# McuPro.net
KiCad netlist of a schematic drawn in Altium Designer
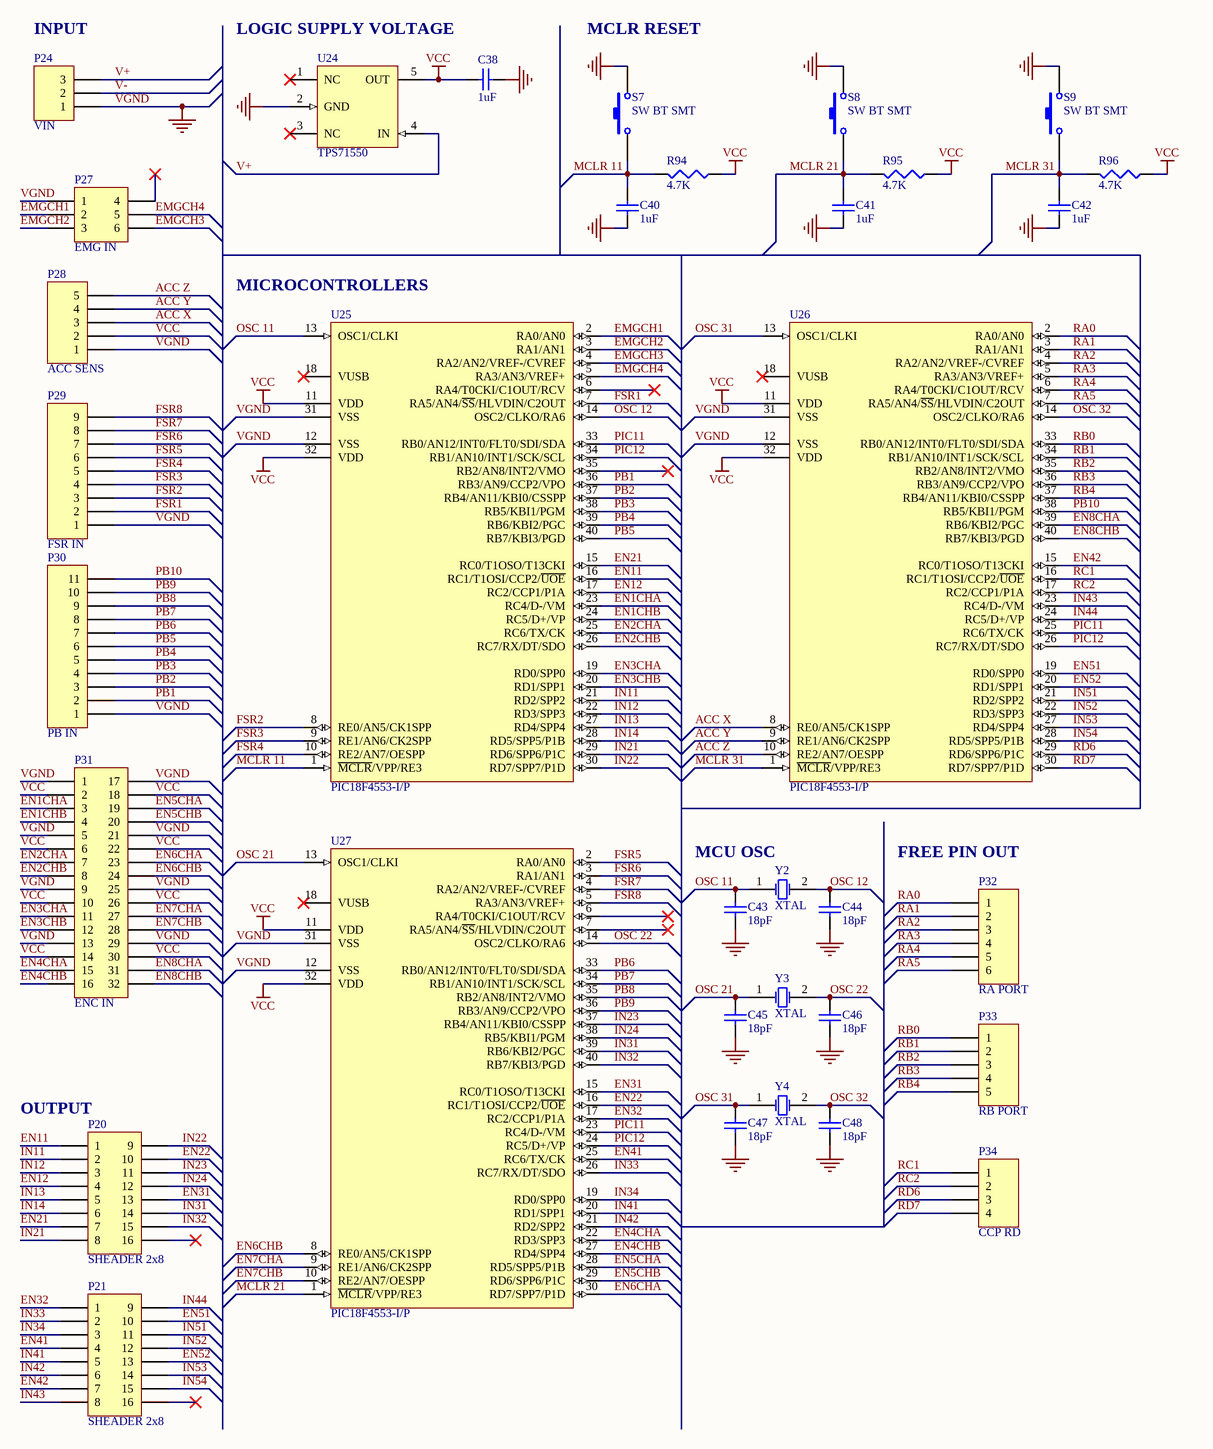
[diagram p0: McuPro.SchDoc]

(export (version "E")
  (design (tool "Eeschema 10.0.6"))
  (components
    (comp (ref "C38")
      (value "1uF")
      (footprint "CAPC2012M")
      (description "Capacitor (Semiconductor SIM Model)")
      (fields (field (name "Comment") "Cap Semi") (field (name "PUBLISHER") "Altium Limited"))
      (libsource (lib "Miscellaneous Devices") (part "Cap Semi"))
    )
    (comp (ref "C40")
      (value "1uF")
      (footprint "CAPC2012M")
      (description "Capacitor (Semiconductor SIM Model)")
      (fields (field (name "Comment") "Cap Semi") (field (name "PUBLISHER") "Altium Limited"))
      (libsource (lib "Miscellaneous Devices") (part "Cap Semi"))
    )
    (comp (ref "C41")
      (value "1uF")
      (footprint "CAPC2012M")
      (description "Capacitor (Semiconductor SIM Model)")
      (fields (field (name "Comment") "Cap Semi") (field (name "PUBLISHER") "Altium Limited"))
      (libsource (lib "Miscellaneous Devices") (part "Cap Semi"))
    )
    (comp (ref "C42")
      (value "1uF")
      (footprint "CAPC2012M")
      (description "Capacitor (Semiconductor SIM Model)")
      (fields (field (name "Comment") "Cap Semi") (field (name "PUBLISHER") "Altium Limited"))
      (libsource (lib "Miscellaneous Devices") (part "Cap Semi"))
    )
    (comp (ref "C43")
      (value "18pF")
      (footprint "C1206")
      (description "Capacitor (Semiconductor SIM Model)")
      (fields (field (name "Comment") "Cap Semi") (field (name "PUBLISHER") "Altium Limited"))
      (libsource (lib "Miscellaneous Devices") (part "Cap Semi"))
    )
    (comp (ref "C44")
      (value "18pF")
      (footprint "C1206")
      (description "Capacitor (Semiconductor SIM Model)")
      (fields (field (name "Comment") "Cap Semi") (field (name "PUBLISHER") "Altium Limited"))
      (libsource (lib "Miscellaneous Devices") (part "Cap Semi"))
    )
    (comp (ref "C45")
      (value "18pF")
      (footprint "C1206")
      (description "Capacitor (Semiconductor SIM Model)")
      (fields (field (name "Comment") "Cap Semi") (field (name "PUBLISHER") "Altium Limited"))
      (libsource (lib "Miscellaneous Devices") (part "Cap Semi"))
    )
    (comp (ref "C46")
      (value "18pF")
      (footprint "C1206")
      (description "Capacitor (Semiconductor SIM Model)")
      (fields (field (name "Comment") "Cap Semi") (field (name "PUBLISHER") "Altium Limited"))
      (libsource (lib "Miscellaneous Devices") (part "Cap Semi"))
    )
    (comp (ref "C47")
      (value "18pF")
      (footprint "C1206")
      (description "Capacitor (Semiconductor SIM Model)")
      (fields (field (name "Comment") "Cap Semi") (field (name "PUBLISHER") "Altium Limited"))
      (libsource (lib "Miscellaneous Devices") (part "Cap Semi"))
    )
    (comp (ref "C48")
      (value "18pF")
      (footprint "C1206")
      (description "Capacitor (Semiconductor SIM Model)")
      (fields (field (name "Comment") "Cap Semi") (field (name "PUBLISHER") "Altium Limited"))
      (libsource (lib "Miscellaneous Devices") (part "Cap Semi"))
    )
    (comp (ref "P20")
      (value "SHEADER 2x8")
      (footprint "SHBH 2X8")
      (description "Shrouded Box Header: 2x8-Pin, 0.100\" (2.54 mm) Male")
      (libsource (lib "LitoLibrary") (part "SB Header 2x8"))
    )
    (comp (ref "P21")
      (value "SHEADER 2x8")
      (footprint "SHBH 2X8")
      (description "Shrouded Box Header: 2x8-Pin, 0.100\" (2.54 mm) Male")
      (libsource (lib "LitoLibrary") (part "SB Header 2x8"))
    )
    (comp (ref "P24")
      (value "VIN")
      (footprint "AZUL5-3")
      (description "Header, 3-Pin")
      (fields (field (name "PUBLISHER") "Altium Limited"))
      (libsource (lib "Miscellaneous Connectors") (part "Header 3"))
    )
    (comp (ref "P27")
      (value "EMG IN")
      (footprint "SHBH 2x3")
      (description "Shrouded Box Header: 2x8-Pin, 0.100\" (2.54 mm) Male")
      (libsource (lib "LitoLibrary") (part "SB Header 2x3"))
    )
    (comp (ref "P28")
      (value "ACC SENS")
      (footprint "HDR1X5H")
      (description "Header, 5-Pin, Right Angle")
      (fields (field (name "PUBLISHER") "Altium Limited"))
      (libsource (lib "Miscellaneous Connectors") (part "Header 5H"))
    )
    (comp (ref "P29")
      (value "FSR IN")
      (footprint "HDR1X9H")
      (description "Header, 9-Pin, Right Angle")
      (fields (field (name "PUBLISHER") "Altium Limited"))
      (libsource (lib "Miscellaneous Connectors") (part "Header 9H"))
    )
    (comp (ref "P30")
      (value "PB IN")
      (footprint "HDR1X11H")
      (description "Header, 11-Pin, Right Angle")
      (fields (field (name "PUBLISHER") "Altium Limited"))
      (libsource (lib "Miscellaneous Connectors") (part "Header 11H"))
    )
    (comp (ref "P31")
      (value "ENC IN")
      (footprint "HDR2X16_CEN")
      (description "Header, 16-Pin, Dual row")
      (fields (field (name "PUBLISHER") "Altium Limited"))
      (libsource (lib "Miscellaneous Connectors") (part "Header 16X2A"))
    )
    (comp (ref "P32")
      (value "RA PORT")
      (footprint "HDR1X6")
      (description "Header, 6-Pin")
      (fields (field (name "PUBLISHER") "Altium Limited"))
      (libsource (lib "Miscellaneous Connectors") (part "Header 6"))
    )
    (comp (ref "P33")
      (value "RB PORT")
      (footprint "HDR1X5")
      (description "Header, 5-Pin")
      (fields (field (name "PUBLISHER") "Altium Limited"))
      (libsource (lib "Miscellaneous Connectors") (part "Header 5"))
    )
    (comp (ref "P34")
      (value "CCP RD")
      (footprint "HDR1X4")
      (description "Header, 4-Pin")
      (fields (field (name "PUBLISHER") "Altium Limited"))
      (libsource (lib "Miscellaneous Connectors") (part "Header 4"))
    )
    (comp (ref "R94")
      (value "4.7K")
      (footprint "RESC3225M")
      (description "Resistor")
      (fields (field (name "Comment") "Res3") (field (name "PUBLISHER") "Altium Limited"))
      (libsource (lib "Miscellaneous Devices") (part "Res3"))
    )
    (comp (ref "R95")
      (value "4.7K")
      (footprint "RESC3225M")
      (description "Resistor")
      (fields (field (name "Comment") "Res3") (field (name "PUBLISHER") "Altium Limited"))
      (libsource (lib "Miscellaneous Devices") (part "Res3"))
    )
    (comp (ref "R96")
      (value "4.7K")
      (footprint "RESC3225M")
      (description "Resistor")
      (fields (field (name "Comment") "Res3") (field (name "PUBLISHER") "Altium Limited"))
      (libsource (lib "Miscellaneous Devices") (part "Res3"))
    )
    (comp (ref "S7")
      (value "SW BT SMT")
      (footprint "PBOTTON SMT4")
      (description "Pushbutton Switches FSM2JSMAASTR=6MM TACT SWITCH,")
      (libsource (lib "LitoLibrary") (part "SW PB 6mm"))
    )
    (comp (ref "S8")
      (value "SW BT SMT")
      (footprint "PBOTTON SMT4")
      (description "Pushbutton Switches FSM2JSMAASTR=6MM TACT SWITCH,")
      (libsource (lib "LitoLibrary") (part "SW PB 6mm"))
    )
    (comp (ref "S9")
      (value "SW BT SMT")
      (footprint "PBOTTON SMT4")
      (description "Pushbutton Switches FSM2JSMAASTR=6MM TACT SWITCH,")
      (libsource (lib "LitoLibrary") (part "SW PB 6mm"))
    )
    (comp (ref "U24")
      (value "TPS71550")
      (footprint "SOT353-5L")
      (libsource (lib "LitoLibrary") (part "TPS71550"))
    )
    (comp (ref "U25")
      (value "PIC18F4553-I/P")
      (footprint "PDIP600-P40")
      (fields (field (name "PUBLISHER") "Altium Limited"))
      (libsource (lib "Microchip Microcontroller 8-Bit PIC18") (part "PIC18F4553-I/P"))
    )
    (comp (ref "U26")
      (value "PIC18F4553-I/P")
      (footprint "PDIP600-P40")
      (fields (field (name "PUBLISHER") "Altium Limited"))
      (libsource (lib "Microchip Microcontroller 8-Bit PIC18") (part "PIC18F4553-I/P"))
    )
    (comp (ref "U27")
      (value "PIC18F4553-I/P")
      (footprint "PDIP600-P40")
      (fields (field (name "PUBLISHER") "Altium Limited"))
      (libsource (lib "Microchip Microcontroller 8-Bit PIC18") (part "PIC18F4553-I/P"))
    )
    (comp (ref "Y2")
      (value "XTAL")
      (footprint "XTAL-1")
      (description "Crystal Oscillator")
      (fields (field (name "PUBLISHER") "Altium Limited"))
      (libsource (lib "Miscellaneous Devices") (part "XTAL"))
    )
    (comp (ref "Y3")
      (value "XTAL")
      (footprint "XTAL-1")
      (description "Crystal Oscillator")
      (fields (field (name "PUBLISHER") "Altium Limited"))
      (libsource (lib "Miscellaneous Devices") (part "XTAL"))
    )
    (comp (ref "Y4")
      (value "XTAL")
      (footprint "XTAL-1")
      (description "Crystal Oscillator")
      (fields (field (name "PUBLISHER") "Altium Limited"))
      (libsource (lib "Miscellaneous Devices") (part "XTAL"))
    )
  )
  (nets
    (net (code "1") (name "/ACC X") (class "Default")
      (node (ref "P28") (pin "3") (pinfunction "3_3") (pintype "passive"))
      (node (ref "U26") (pin "8") (pinfunction "RE0/AN5/CK1SPP_8") (pintype "bidirectional"))
    )
    (net (code "2") (name "/ACC Y") (class "Default")
      (node (ref "P28") (pin "4") (pinfunction "4_4") (pintype "passive"))
      (node (ref "U26") (pin "9") (pinfunction "RE1/AN6/CK2SPP_9") (pintype "bidirectional"))
    )
    (net (code "3") (name "/ACC Z") (class "Default")
      (node (ref "P28") (pin "5") (pinfunction "5_5") (pintype "passive"))
      (node (ref "U26") (pin "10") (pinfunction "RE2/AN7/OESPP_10") (pintype "bidirectional"))
    )
    (net (code "4") (name "/EMGCH1") (class "Default")
      (node (ref "P27") (pin "2") (pinfunction "2_2") (pintype "passive"))
      (node (ref "U25") (pin "2") (pinfunction "RA0/AN0_2") (pintype "bidirectional"))
    )
    (net (code "5") (name "/EMGCH2") (class "Default")
      (node (ref "P27") (pin "3") (pinfunction "3_3") (pintype "passive"))
      (node (ref "U25") (pin "3") (pinfunction "RA1/AN1_3") (pintype "bidirectional"))
    )
    (net (code "6") (name "/EMGCH3") (class "Default")
      (node (ref "P27") (pin "6") (pinfunction "6_6") (pintype "passive"))
      (node (ref "U25") (pin "4") (pinfunction "RA2/AN2/VREF-/CVREF_4") (pintype "bidirectional"))
    )
    (net (code "7") (name "/EMGCH4") (class "Default")
      (node (ref "P27") (pin "5") (pinfunction "5_5") (pintype "passive"))
      (node (ref "U25") (pin "5") (pinfunction "RA3/AN3/VREF+_5") (pintype "bidirectional"))
    )
    (net (code "8") (name "/EN1CHA") (class "Default")
      (node (ref "P31") (pin "3") (pinfunction "3_3") (pintype "passive"))
      (node (ref "U25") (pin "23") (pinfunction "RC4/D-/VM_23") (pintype "bidirectional"))
    )
    (net (code "9") (name "/EN1CHB") (class "Default")
      (node (ref "P31") (pin "4") (pinfunction "4_4") (pintype "passive"))
      (node (ref "U25") (pin "24") (pinfunction "RC5/D+/VP_24") (pintype "bidirectional"))
    )
    (net (code "10") (name "/EN2CHA") (class "Default")
      (node (ref "P31") (pin "7") (pinfunction "7_7") (pintype "passive"))
      (node (ref "U25") (pin "25") (pinfunction "RC6/TX/CK_25") (pintype "bidirectional"))
    )
    (net (code "11") (name "/EN2CHB") (class "Default")
      (node (ref "P31") (pin "8") (pinfunction "8_8") (pintype "passive"))
      (node (ref "U25") (pin "26") (pinfunction "RC7/RX/DT/SDO_26") (pintype "bidirectional"))
    )
    (net (code "12") (name "/EN3CHA") (class "Default")
      (node (ref "P31") (pin "11") (pinfunction "11_11") (pintype "passive"))
      (node (ref "U25") (pin "19") (pinfunction "RD0/SPP0_19") (pintype "bidirectional"))
    )
    (net (code "13") (name "/EN3CHB") (class "Default")
      (node (ref "P31") (pin "12") (pinfunction "12_12") (pintype "passive"))
      (node (ref "U25") (pin "20") (pinfunction "RD1/SPP1_20") (pintype "bidirectional"))
    )
    (net (code "14") (name "/EN4CHA") (class "Default")
      (node (ref "P31") (pin "15") (pinfunction "15_15") (pintype "passive"))
      (node (ref "U27") (pin "22") (pinfunction "RD3/SPP3_22") (pintype "bidirectional"))
    )
    (net (code "15") (name "/EN4CHB") (class "Default")
      (node (ref "P31") (pin "16") (pinfunction "16_16") (pintype "passive"))
      (node (ref "U27") (pin "27") (pinfunction "RD4/SPP4_27") (pintype "bidirectional"))
    )
    (net (code "16") (name "/EN5CHA") (class "Default")
      (node (ref "P31") (pin "19") (pinfunction "19_19") (pintype "passive"))
      (node (ref "U27") (pin "28") (pinfunction "RD5/SPP5/P1B_28") (pintype "bidirectional"))
    )
    (net (code "17") (name "/EN5CHB") (class "Default")
      (node (ref "P31") (pin "20") (pinfunction "20_20") (pintype "passive"))
      (node (ref "U27") (pin "29") (pinfunction "RD6/SPP6/P1C_29") (pintype "bidirectional"))
    )
    (net (code "18") (name "/EN6CHA") (class "Default")
      (node (ref "P31") (pin "23") (pinfunction "23_23") (pintype "passive"))
      (node (ref "U27") (pin "30") (pinfunction "RD7/SPP7/P1D_30") (pintype "bidirectional"))
    )
    (net (code "19") (name "/EN6CHB") (class "Default")
      (node (ref "P31") (pin "24") (pinfunction "24_24") (pintype "passive"))
      (node (ref "U27") (pin "8") (pinfunction "RE0/AN5/CK1SPP_8") (pintype "bidirectional"))
    )
    (net (code "20") (name "/EN7CHA") (class "Default")
      (node (ref "P31") (pin "27") (pinfunction "27_27") (pintype "passive"))
      (node (ref "U27") (pin "9") (pinfunction "RE1/AN6/CK2SPP_9") (pintype "bidirectional"))
    )
    (net (code "21") (name "/EN7CHB") (class "Default")
      (node (ref "P31") (pin "28") (pinfunction "28_28") (pintype "passive"))
      (node (ref "U27") (pin "10") (pinfunction "RE2/AN7/OESPP_10") (pintype "bidirectional"))
    )
    (net (code "22") (name "/EN8CHA") (class "Default")
      (node (ref "P31") (pin "31") (pinfunction "31_31") (pintype "passive"))
      (node (ref "U26") (pin "39") (pinfunction "RB6/KBI2/PGC_39") (pintype "bidirectional"))
    )
    (net (code "23") (name "/EN8CHB") (class "Default")
      (node (ref "P31") (pin "32") (pinfunction "32_32") (pintype "passive"))
      (node (ref "U26") (pin "40") (pinfunction "RB7/KBI3/PGD_40") (pintype "bidirectional"))
    )
    (net (code "24") (name "/EN11") (class "Default")
      (node (ref "P20") (pin "1") (pinfunction "1_1") (pintype "passive"))
      (node (ref "U25") (pin "16") (pinfunction "RC1/T1OSI/CCP2/~{UOE}_16") (pintype "bidirectional"))
    )
    (net (code "25") (name "/EN12") (class "Default")
      (node (ref "P20") (pin "4") (pinfunction "4_4") (pintype "passive"))
      (node (ref "U25") (pin "17") (pinfunction "RC2/CCP1/P1A_17") (pintype "bidirectional"))
    )
    (net (code "26") (name "/EN21") (class "Default")
      (node (ref "P20") (pin "7") (pinfunction "7_7") (pintype "passive"))
      (node (ref "U25") (pin "15") (pinfunction "RC0/T1OSO/T13CKI_15") (pintype "bidirectional"))
    )
    (net (code "27") (name "/EN22") (class "Default")
      (node (ref "P20") (pin "10") (pinfunction "10_10") (pintype "passive"))
      (node (ref "U27") (pin "16") (pinfunction "RC1/T1OSI/CCP2/~{UOE}_16") (pintype "bidirectional"))
    )
    (net (code "28") (name "/EN31") (class "Default")
      (node (ref "P20") (pin "13") (pinfunction "13_13") (pintype "passive"))
      (node (ref "U27") (pin "15") (pinfunction "RC0/T1OSO/T13CKI_15") (pintype "bidirectional"))
    )
    (net (code "29") (name "/EN32") (class "Default")
      (node (ref "P21") (pin "1") (pinfunction "1_1") (pintype "passive"))
      (node (ref "U27") (pin "17") (pinfunction "RC2/CCP1/P1A_17") (pintype "bidirectional"))
    )
    (net (code "30") (name "/EN41") (class "Default")
      (node (ref "P21") (pin "4") (pinfunction "4_4") (pintype "passive"))
      (node (ref "U27") (pin "25") (pinfunction "RC6/TX/CK_25") (pintype "bidirectional"))
    )
    (net (code "31") (name "/EN42") (class "Default")
      (node (ref "P21") (pin "7") (pinfunction "7_7") (pintype "passive"))
      (node (ref "U26") (pin "15") (pinfunction "RC0/T1OSO/T13CKI_15") (pintype "bidirectional"))
    )
    (net (code "32") (name "/EN51") (class "Default")
      (node (ref "P21") (pin "10") (pinfunction "10_10") (pintype "passive"))
      (node (ref "U26") (pin "19") (pinfunction "RD0/SPP0_19") (pintype "bidirectional"))
    )
    (net (code "33") (name "/EN52") (class "Default")
      (node (ref "P21") (pin "13") (pinfunction "13_13") (pintype "passive"))
      (node (ref "U26") (pin "20") (pinfunction "RD1/SPP1_20") (pintype "bidirectional"))
    )
    (net (code "34") (name "/FSR1") (class "Default")
      (node (ref "P29") (pin "2") (pinfunction "2_2") (pintype "passive"))
      (node (ref "U25") (pin "7") (pinfunction "RA5/AN4/~{SS}/HLVDIN/C2OUT_7") (pintype "bidirectional"))
    )
    (net (code "35") (name "/FSR2") (class "Default")
      (node (ref "P29") (pin "3") (pinfunction "3_3") (pintype "passive"))
      (node (ref "U25") (pin "8") (pinfunction "RE0/AN5/CK1SPP_8") (pintype "bidirectional"))
    )
    (net (code "36") (name "/FSR3") (class "Default")
      (node (ref "P29") (pin "4") (pinfunction "4_4") (pintype "passive"))
      (node (ref "U25") (pin "9") (pinfunction "RE1/AN6/CK2SPP_9") (pintype "bidirectional"))
    )
    (net (code "37") (name "/FSR4") (class "Default")
      (node (ref "P29") (pin "5") (pinfunction "5_5") (pintype "passive"))
      (node (ref "U25") (pin "10") (pinfunction "RE2/AN7/OESPP_10") (pintype "bidirectional"))
    )
    (net (code "38") (name "/FSR5") (class "Default")
      (node (ref "P29") (pin "6") (pinfunction "6_6") (pintype "passive"))
      (node (ref "U27") (pin "2") (pinfunction "RA0/AN0_2") (pintype "bidirectional"))
    )
    (net (code "39") (name "/FSR6") (class "Default")
      (node (ref "P29") (pin "7") (pinfunction "7_7") (pintype "passive"))
      (node (ref "U27") (pin "3") (pinfunction "RA1/AN1_3") (pintype "bidirectional"))
    )
    (net (code "40") (name "/FSR7") (class "Default")
      (node (ref "P29") (pin "8") (pinfunction "8_8") (pintype "passive"))
      (node (ref "U27") (pin "4") (pinfunction "RA2/AN2/VREF-/CVREF_4") (pintype "bidirectional"))
    )
    (net (code "41") (name "/FSR8") (class "Default")
      (node (ref "P29") (pin "9") (pinfunction "9_9") (pintype "passive"))
      (node (ref "U27") (pin "5") (pinfunction "RA3/AN3/VREF+_5") (pintype "bidirectional"))
    )
    (net (code "42") (name "/IN11") (class "Default")
      (node (ref "P20") (pin "2") (pinfunction "2_2") (pintype "passive"))
      (node (ref "U25") (pin "21") (pinfunction "RD2/SPP2_21") (pintype "bidirectional"))
    )
    (net (code "43") (name "/IN12") (class "Default")
      (node (ref "P20") (pin "3") (pinfunction "3_3") (pintype "passive"))
      (node (ref "U25") (pin "22") (pinfunction "RD3/SPP3_22") (pintype "bidirectional"))
    )
    (net (code "44") (name "/IN13") (class "Default")
      (node (ref "P20") (pin "5") (pinfunction "5_5") (pintype "passive"))
      (node (ref "U25") (pin "27") (pinfunction "RD4/SPP4_27") (pintype "bidirectional"))
    )
    (net (code "45") (name "/IN14") (class "Default")
      (node (ref "P20") (pin "6") (pinfunction "6_6") (pintype "passive"))
      (node (ref "U25") (pin "28") (pinfunction "RD5/SPP5/P1B_28") (pintype "bidirectional"))
    )
    (net (code "46") (name "/IN21") (class "Default")
      (node (ref "P20") (pin "8") (pinfunction "8_8") (pintype "passive"))
      (node (ref "U25") (pin "29") (pinfunction "RD6/SPP6/P1C_29") (pintype "bidirectional"))
    )
    (net (code "47") (name "/IN22") (class "Default")
      (node (ref "P20") (pin "9") (pinfunction "9_9") (pintype "passive"))
      (node (ref "U25") (pin "30") (pinfunction "RD7/SPP7/P1D_30") (pintype "bidirectional"))
    )
    (net (code "48") (name "/IN23") (class "Default")
      (node (ref "P20") (pin "11") (pinfunction "11_11") (pintype "passive"))
      (node (ref "U27") (pin "37") (pinfunction "RB4/AN11/KBI0/CSSPP_37") (pintype "bidirectional"))
    )
    (net (code "49") (name "/IN24") (class "Default")
      (node (ref "P20") (pin "12") (pinfunction "12_12") (pintype "passive"))
      (node (ref "U27") (pin "38") (pinfunction "RB5/KBI1/PGM_38") (pintype "bidirectional"))
    )
    (net (code "50") (name "/IN31") (class "Default")
      (node (ref "P20") (pin "14") (pinfunction "14_14") (pintype "passive"))
      (node (ref "U27") (pin "39") (pinfunction "RB6/KBI2/PGC_39") (pintype "bidirectional"))
    )
    (net (code "51") (name "/IN32") (class "Default")
      (node (ref "P20") (pin "15") (pinfunction "15_15") (pintype "passive"))
      (node (ref "U27") (pin "40") (pinfunction "RB7/KBI3/PGD_40") (pintype "bidirectional"))
    )
    (net (code "52") (name "/IN33") (class "Default")
      (node (ref "P21") (pin "2") (pinfunction "2_2") (pintype "passive"))
      (node (ref "U27") (pin "26") (pinfunction "RC7/RX/DT/SDO_26") (pintype "bidirectional"))
    )
    (net (code "53") (name "/IN34") (class "Default")
      (node (ref "P21") (pin "3") (pinfunction "3_3") (pintype "passive"))
      (node (ref "U27") (pin "19") (pinfunction "RD0/SPP0_19") (pintype "bidirectional"))
    )
    (net (code "54") (name "/IN41") (class "Default")
      (node (ref "P21") (pin "5") (pinfunction "5_5") (pintype "passive"))
      (node (ref "U27") (pin "20") (pinfunction "RD1/SPP1_20") (pintype "bidirectional"))
    )
    (net (code "55") (name "/IN42") (class "Default")
      (node (ref "P21") (pin "6") (pinfunction "6_6") (pintype "passive"))
      (node (ref "U27") (pin "21") (pinfunction "RD2/SPP2_21") (pintype "bidirectional"))
    )
    (net (code "56") (name "/IN43") (class "Default")
      (node (ref "P21") (pin "8") (pinfunction "8_8") (pintype "passive"))
      (node (ref "U26") (pin "23") (pinfunction "RC4/D-/VM_23") (pintype "bidirectional"))
    )
    (net (code "57") (name "/IN44") (class "Default")
      (node (ref "P21") (pin "9") (pinfunction "9_9") (pintype "passive"))
      (node (ref "U26") (pin "24") (pinfunction "RC5/D+/VP_24") (pintype "bidirectional"))
    )
    (net (code "58") (name "/IN51") (class "Default")
      (node (ref "P21") (pin "11") (pinfunction "11_11") (pintype "passive"))
      (node (ref "U26") (pin "21") (pinfunction "RD2/SPP2_21") (pintype "bidirectional"))
    )
    (net (code "59") (name "/IN52") (class "Default")
      (node (ref "P21") (pin "12") (pinfunction "12_12") (pintype "passive"))
      (node (ref "U26") (pin "22") (pinfunction "RD3/SPP3_22") (pintype "bidirectional"))
    )
    (net (code "60") (name "/IN53") (class "Default")
      (node (ref "P21") (pin "14") (pinfunction "14_14") (pintype "passive"))
      (node (ref "U26") (pin "27") (pinfunction "RD4/SPP4_27") (pintype "bidirectional"))
    )
    (net (code "61") (name "/IN54") (class "Default")
      (node (ref "P21") (pin "15") (pinfunction "15_15") (pintype "passive"))
      (node (ref "U26") (pin "28") (pinfunction "RD5/SPP5/P1B_28") (pintype "bidirectional"))
    )
    (net (code "62") (name "/MCLR 11") (class "Default")
      (node (ref "C40") (pin "1") (pinfunction "1_1") (pintype "passive"))
      (node (ref "R94") (pin "2") (pinfunction "2_2") (pintype "passive"))
      (node (ref "S7") (pin "1") (pinfunction "1_1") (pintype "passive"))
      (node (ref "U25") (pin "1") (pinfunction "~{MCLR}/VPP/RE3_1") (pintype "input"))
    )
    (net (code "63") (name "/MCLR 21") (class "Default")
      (node (ref "C41") (pin "1") (pinfunction "1_1") (pintype "passive"))
      (node (ref "R95") (pin "2") (pinfunction "2_2") (pintype "passive"))
      (node (ref "S8") (pin "1") (pinfunction "1_1") (pintype "passive"))
      (node (ref "U27") (pin "1") (pinfunction "~{MCLR}/VPP/RE3_1") (pintype "input"))
    )
    (net (code "64") (name "/MCLR 31") (class "Default")
      (node (ref "C42") (pin "1") (pinfunction "1_1") (pintype "passive"))
      (node (ref "R96") (pin "2") (pinfunction "2_2") (pintype "passive"))
      (node (ref "S9") (pin "1") (pinfunction "1_1") (pintype "passive"))
      (node (ref "U26") (pin "1") (pinfunction "~{MCLR}/VPP/RE3_1") (pintype "input"))
    )
    (net (code "65") (name "/OSC 11") (class "Default")
      (node (ref "C43") (pin "1") (pinfunction "1_1") (pintype "passive"))
      (node (ref "U25") (pin "13") (pinfunction "OSC1/CLKI_13") (pintype "input"))
      (node (ref "Y2") (pin "1") (pinfunction "OSC1_1") (pintype "passive"))
    )
    (net (code "66") (name "/OSC 12") (class "Default")
      (node (ref "C44") (pin "1") (pinfunction "1_1") (pintype "passive"))
      (node (ref "U25") (pin "14") (pinfunction "OSC2/CLKO/RA6_14") (pintype "bidirectional"))
      (node (ref "Y2") (pin "2") (pinfunction "OSC2_2") (pintype "passive"))
    )
    (net (code "67") (name "/OSC 21") (class "Default")
      (node (ref "C45") (pin "1") (pinfunction "1_1") (pintype "passive"))
      (node (ref "U27") (pin "13") (pinfunction "OSC1/CLKI_13") (pintype "input"))
      (node (ref "Y3") (pin "1") (pinfunction "OSC1_1") (pintype "passive"))
    )
    (net (code "68") (name "/OSC 22") (class "Default")
      (node (ref "C46") (pin "1") (pinfunction "1_1") (pintype "passive"))
      (node (ref "U27") (pin "14") (pinfunction "OSC2/CLKO/RA6_14") (pintype "bidirectional"))
      (node (ref "Y3") (pin "2") (pinfunction "OSC2_2") (pintype "passive"))
    )
    (net (code "69") (name "/OSC 31") (class "Default")
      (node (ref "C47") (pin "1") (pinfunction "1_1") (pintype "passive"))
      (node (ref "U26") (pin "13") (pinfunction "OSC1/CLKI_13") (pintype "input"))
      (node (ref "Y4") (pin "1") (pinfunction "OSC1_1") (pintype "passive"))
    )
    (net (code "70") (name "/OSC 32") (class "Default")
      (node (ref "C48") (pin "1") (pinfunction "1_1") (pintype "passive"))
      (node (ref "U26") (pin "14") (pinfunction "OSC2/CLKO/RA6_14") (pintype "bidirectional"))
      (node (ref "Y4") (pin "2") (pinfunction "OSC2_2") (pintype "passive"))
    )
    (net (code "71") (name "/PB1") (class "Default")
      (node (ref "P30") (pin "2") (pinfunction "2_2") (pintype "passive"))
      (node (ref "U25") (pin "36") (pinfunction "RB3/AN9/CCP2/VPO_36") (pintype "bidirectional"))
    )
    (net (code "72") (name "/PB2") (class "Default")
      (node (ref "P30") (pin "3") (pinfunction "3_3") (pintype "passive"))
      (node (ref "U25") (pin "37") (pinfunction "RB4/AN11/KBI0/CSSPP_37") (pintype "bidirectional"))
    )
    (net (code "73") (name "/PB3") (class "Default")
      (node (ref "P30") (pin "4") (pinfunction "4_4") (pintype "passive"))
      (node (ref "U25") (pin "38") (pinfunction "RB5/KBI1/PGM_38") (pintype "bidirectional"))
    )
    (net (code "74") (name "/PB4") (class "Default")
      (node (ref "P30") (pin "5") (pinfunction "5_5") (pintype "passive"))
      (node (ref "U25") (pin "39") (pinfunction "RB6/KBI2/PGC_39") (pintype "bidirectional"))
    )
    (net (code "75") (name "/PB5") (class "Default")
      (node (ref "P30") (pin "6") (pinfunction "6_6") (pintype "passive"))
      (node (ref "U25") (pin "40") (pinfunction "RB7/KBI3/PGD_40") (pintype "bidirectional"))
    )
    (net (code "76") (name "/PB6") (class "Default")
      (node (ref "P30") (pin "7") (pinfunction "7_7") (pintype "passive"))
      (node (ref "U27") (pin "33") (pinfunction "RB0/AN12/INT0/FLT0/SDI/SDA_33") (pintype "bidirectional"))
    )
    (net (code "77") (name "/PB7") (class "Default")
      (node (ref "P30") (pin "8") (pinfunction "8_8") (pintype "passive"))
      (node (ref "U27") (pin "34") (pinfunction "RB1/AN10/INT1/SCK/SCL_34") (pintype "bidirectional"))
    )
    (net (code "78") (name "/PB8") (class "Default")
      (node (ref "P30") (pin "9") (pinfunction "9_9") (pintype "passive"))
      (node (ref "U27") (pin "35") (pinfunction "RB2/AN8/INT2/VMO_35") (pintype "bidirectional"))
    )
    (net (code "79") (name "/PB9") (class "Default")
      (node (ref "P30") (pin "10") (pinfunction "10_10") (pintype "passive"))
      (node (ref "U27") (pin "36") (pinfunction "RB3/AN9/CCP2/VPO_36") (pintype "bidirectional"))
    )
    (net (code "80") (name "/PB10") (class "Default")
      (node (ref "P30") (pin "11") (pinfunction "11_11") (pintype "passive"))
      (node (ref "U26") (pin "38") (pinfunction "RB5/KBI1/PGM_38") (pintype "bidirectional"))
    )
    (net (code "81") (name "/PIC11") (class "Default")
      (node (ref "U25") (pin "33") (pinfunction "RB0/AN12/INT0/FLT0/SDI/SDA_33") (pintype "bidirectional"))
      (node (ref "U26") (pin "25") (pinfunction "RC6/TX/CK_25") (pintype "bidirectional"))
      (node (ref "U27") (pin "23") (pinfunction "RC4/D-/VM_23") (pintype "bidirectional"))
    )
    (net (code "82") (name "/PIC12") (class "Default")
      (node (ref "U25") (pin "34") (pinfunction "RB1/AN10/INT1/SCK/SCL_34") (pintype "bidirectional"))
      (node (ref "U26") (pin "26") (pinfunction "RC7/RX/DT/SDO_26") (pintype "bidirectional"))
      (node (ref "U27") (pin "24") (pinfunction "RC5/D+/VP_24") (pintype "bidirectional"))
    )
    (net (code "83") (name "/RA0") (class "Default")
      (node (ref "P32") (pin "1") (pinfunction "1_1") (pintype "passive"))
      (node (ref "U26") (pin "2") (pinfunction "RA0/AN0_2") (pintype "bidirectional"))
    )
    (net (code "84") (name "/RA1") (class "Default")
      (node (ref "P32") (pin "2") (pinfunction "2_2") (pintype "passive"))
      (node (ref "U26") (pin "3") (pinfunction "RA1/AN1_3") (pintype "bidirectional"))
    )
    (net (code "85") (name "/RA2") (class "Default")
      (node (ref "P32") (pin "3") (pinfunction "3_3") (pintype "passive"))
      (node (ref "U26") (pin "4") (pinfunction "RA2/AN2/VREF-/CVREF_4") (pintype "bidirectional"))
    )
    (net (code "86") (name "/RA3") (class "Default")
      (node (ref "P32") (pin "4") (pinfunction "4_4") (pintype "passive"))
      (node (ref "U26") (pin "5") (pinfunction "RA3/AN3/VREF+_5") (pintype "bidirectional"))
    )
    (net (code "87") (name "/RA4") (class "Default")
      (node (ref "P32") (pin "5") (pinfunction "5_5") (pintype "passive"))
      (node (ref "U26") (pin "6") (pinfunction "RA4/T0CKI/C1OUT/RCV_6") (pintype "bidirectional"))
    )
    (net (code "88") (name "/RA5") (class "Default")
      (node (ref "P32") (pin "6") (pinfunction "6_6") (pintype "passive"))
      (node (ref "U26") (pin "7") (pinfunction "RA5/AN4/~{SS}/HLVDIN/C2OUT_7") (pintype "bidirectional"))
    )
    (net (code "89") (name "/RB0") (class "Default")
      (node (ref "P33") (pin "1") (pinfunction "1_1") (pintype "passive"))
      (node (ref "U26") (pin "33") (pinfunction "RB0/AN12/INT0/FLT0/SDI/SDA_33") (pintype "bidirectional"))
    )
    (net (code "90") (name "/RB1") (class "Default")
      (node (ref "P33") (pin "2") (pinfunction "2_2") (pintype "passive"))
      (node (ref "U26") (pin "34") (pinfunction "RB1/AN10/INT1/SCK/SCL_34") (pintype "bidirectional"))
    )
    (net (code "91") (name "/RB2") (class "Default")
      (node (ref "P33") (pin "3") (pinfunction "3_3") (pintype "passive"))
      (node (ref "U26") (pin "35") (pinfunction "RB2/AN8/INT2/VMO_35") (pintype "bidirectional"))
    )
    (net (code "92") (name "/RB3") (class "Default")
      (node (ref "P33") (pin "4") (pinfunction "4_4") (pintype "passive"))
      (node (ref "U26") (pin "36") (pinfunction "RB3/AN9/CCP2/VPO_36") (pintype "bidirectional"))
    )
    (net (code "93") (name "/RB4") (class "Default")
      (node (ref "P33") (pin "5") (pinfunction "5_5") (pintype "passive"))
      (node (ref "U26") (pin "37") (pinfunction "RB4/AN11/KBI0/CSSPP_37") (pintype "bidirectional"))
    )
    (net (code "94") (name "/RC1") (class "Default")
      (node (ref "P34") (pin "1") (pinfunction "1_1") (pintype "passive"))
      (node (ref "U26") (pin "16") (pinfunction "RC1/T1OSI/CCP2/~{UOE}_16") (pintype "bidirectional"))
    )
    (net (code "95") (name "/RC2") (class "Default")
      (node (ref "P34") (pin "2") (pinfunction "2_2") (pintype "passive"))
      (node (ref "U26") (pin "17") (pinfunction "RC2/CCP1/P1A_17") (pintype "bidirectional"))
    )
    (net (code "96") (name "/RD6") (class "Default")
      (node (ref "P34") (pin "3") (pinfunction "3_3") (pintype "passive"))
      (node (ref "U26") (pin "29") (pinfunction "RD6/SPP6/P1C_29") (pintype "bidirectional"))
    )
    (net (code "97") (name "/RD7") (class "Default")
      (node (ref "P34") (pin "4") (pinfunction "4_4") (pintype "passive"))
      (node (ref "U26") (pin "30") (pinfunction "RD7/SPP7/P1D_30") (pintype "bidirectional"))
    )
    (net (code "98") (name "/V+") (class "Default")
      (node (ref "P24") (pin "3") (pinfunction "3_3") (pintype "passive"))
      (node (ref "U24") (pin "4") (pinfunction "IN_4") (pintype "input"))
    )
    (net (code "99") (name "/V-") (class "Default")
      (node (ref "P24") (pin "2") (pinfunction "2_2") (pintype "passive"))
    )
    (net (code "100") (name "GND") (class "Default")
      (node (ref "C38") (pin "2") (pinfunction "2_2") (pintype "passive"))
      (node (ref "C40") (pin "2") (pinfunction "2_2") (pintype "passive"))
      (node (ref "C41") (pin "2") (pinfunction "2_2") (pintype "passive"))
      (node (ref "C42") (pin "2") (pinfunction "2_2") (pintype "passive"))
      (node (ref "C43") (pin "2") (pinfunction "2_2") (pintype "passive"))
      (node (ref "C44") (pin "2") (pinfunction "2_2") (pintype "passive"))
      (node (ref "C45") (pin "2") (pinfunction "2_2") (pintype "passive"))
      (node (ref "C46") (pin "2") (pinfunction "2_2") (pintype "passive"))
      (node (ref "C47") (pin "2") (pinfunction "2_2") (pintype "passive"))
      (node (ref "C48") (pin "2") (pinfunction "2_2") (pintype "passive"))
      (node (ref "P24") (pin "1") (pinfunction "1_1") (pintype "passive"))
      (node (ref "P27") (pin "1") (pinfunction "1_1") (pintype "passive"))
      (node (ref "P28") (pin "1") (pinfunction "1_1") (pintype "passive"))
      (node (ref "P29") (pin "1") (pinfunction "1_1") (pintype "passive"))
      (node (ref "P30") (pin "1") (pinfunction "1_1") (pintype "passive"))
      (node (ref "P31") (pin "1") (pinfunction "1_1") (pintype "passive"))
      (node (ref "P31") (pin "13") (pinfunction "13_13") (pintype "passive"))
      (node (ref "P31") (pin "17") (pinfunction "17_17") (pintype "passive"))
      (node (ref "P31") (pin "21") (pinfunction "21_21") (pintype "passive"))
      (node (ref "P31") (pin "25") (pinfunction "25_25") (pintype "passive"))
      (node (ref "P31") (pin "29") (pinfunction "29_29") (pintype "passive"))
      (node (ref "P31") (pin "5") (pinfunction "5_5") (pintype "passive"))
      (node (ref "P31") (pin "9") (pinfunction "9_9") (pintype "passive"))
      (node (ref "S7") (pin "2") (pinfunction "2_2") (pintype "passive"))
      (node (ref "S8") (pin "2") (pinfunction "2_2") (pintype "passive"))
      (node (ref "S9") (pin "2") (pinfunction "2_2") (pintype "passive"))
      (node (ref "U24") (pin "2") (pinfunction "GND_2") (pintype "input"))
      (node (ref "U25") (pin "12") (pinfunction "VSS_12") (pintype "power_in"))
      (node (ref "U25") (pin "31") (pinfunction "VSS_31") (pintype "power_in"))
      (node (ref "U26") (pin "12") (pinfunction "VSS_12") (pintype "power_in"))
      (node (ref "U26") (pin "31") (pinfunction "VSS_31") (pintype "power_in"))
      (node (ref "U27") (pin "12") (pinfunction "VSS_12") (pintype "power_in"))
      (node (ref "U27") (pin "31") (pinfunction "VSS_31") (pintype "power_in"))
    )
    (net (code "101") (name "VCC") (class "Default")
      (node (ref "C38") (pin "1") (pinfunction "1_1") (pintype "passive"))
      (node (ref "P28") (pin "2") (pinfunction "2_2") (pintype "passive"))
      (node (ref "P31") (pin "10") (pinfunction "10_10") (pintype "passive"))
      (node (ref "P31") (pin "14") (pinfunction "14_14") (pintype "passive"))
      (node (ref "P31") (pin "18") (pinfunction "18_18") (pintype "passive"))
      (node (ref "P31") (pin "2") (pinfunction "2_2") (pintype "passive"))
      (node (ref "P31") (pin "22") (pinfunction "22_22") (pintype "passive"))
      (node (ref "P31") (pin "26") (pinfunction "26_26") (pintype "passive"))
      (node (ref "P31") (pin "30") (pinfunction "30_30") (pintype "passive"))
      (node (ref "P31") (pin "6") (pinfunction "6_6") (pintype "passive"))
      (node (ref "R94") (pin "1") (pinfunction "1_1") (pintype "passive"))
      (node (ref "R95") (pin "1") (pinfunction "1_1") (pintype "passive"))
      (node (ref "R96") (pin "1") (pinfunction "1_1") (pintype "passive"))
      (node (ref "U24") (pin "5") (pinfunction "OUT_5") (pintype "passive"))
      (node (ref "U25") (pin "11") (pinfunction "VDD_11") (pintype "power_in"))
      (node (ref "U25") (pin "32") (pinfunction "VDD_32") (pintype "power_in"))
      (node (ref "U26") (pin "11") (pinfunction "VDD_11") (pintype "power_in"))
      (node (ref "U26") (pin "32") (pinfunction "VDD_32") (pintype "power_in"))
      (node (ref "U27") (pin "11") (pinfunction "VDD_11") (pintype "power_in"))
      (node (ref "U27") (pin "32") (pinfunction "VDD_32") (pintype "power_in"))
    )
    (net (code "102") (name "unconnected-(P20-Pad16)") (class "Default")
      (node (ref "P20") (pin "16") (pinfunction "16_16") (pintype "passive+no_connect"))
    )
    (net (code "103") (name "unconnected-(P21-Pad16)") (class "Default")
      (node (ref "P21") (pin "16") (pinfunction "16_16") (pintype "passive+no_connect"))
    )
    (net (code "104") (name "unconnected-(P27-Pad4)") (class "Default")
      (node (ref "P27") (pin "4") (pinfunction "4_4") (pintype "passive+no_connect"))
    )
    (net (code "105") (name "unconnected-(U24-NC-Pad1)") (class "Default")
      (node (ref "U24") (pin "1") (pinfunction "NC_1") (pintype "passive+no_connect"))
    )
    (net (code "106") (name "unconnected-(U24-NC-Pad3)") (class "Default")
      (node (ref "U24") (pin "3") (pinfunction "NC_3") (pintype "passive+no_connect"))
    )
    (net (code "107") (name "unconnected-(U25-RA4{slash}T0CKI{slash}C1OUT{slash}RCV-Pad6)") (class "Default")
      (node (ref "U25") (pin "6") (pinfunction "RA4/T0CKI/C1OUT/RCV_6") (pintype "bidirectional+no_connect"))
    )
    (net (code "108") (name "unconnected-(U25-RB2{slash}AN8{slash}INT2{slash}VMO-Pad35)") (class "Default")
      (node (ref "U25") (pin "35") (pinfunction "RB2/AN8/INT2/VMO_35") (pintype "bidirectional+no_connect"))
    )
    (net (code "109") (name "unconnected-(U25-VUSB-Pad18)") (class "Default")
      (node (ref "U25") (pin "18") (pinfunction "VUSB_18") (pintype "power_in+no_connect"))
    )
    (net (code "110") (name "unconnected-(U26-VUSB-Pad18)") (class "Default")
      (node (ref "U26") (pin "18") (pinfunction "VUSB_18") (pintype "power_in+no_connect"))
    )
    (net (code "111") (name "unconnected-(U27-RA4{slash}T0CKI{slash}C1OUT{slash}RCV-Pad6)") (class "Default")
      (node (ref "U27") (pin "6") (pinfunction "RA4/T0CKI/C1OUT/RCV_6") (pintype "bidirectional+no_connect"))
    )
    (net (code "112") (name "unconnected-(U27-RA5{slash}AN4{slash}~{SS}{slash}HLVDIN{slash}C2OUT-Pad7)") (class "Default")
      (node (ref "U27") (pin "7") (pinfunction "RA5/AN4/~{SS}/HLVDIN/C2OUT_7") (pintype "bidirectional+no_connect"))
    )
    (net (code "113") (name "unconnected-(U27-VUSB-Pad18)") (class "Default")
      (node (ref "U27") (pin "18") (pinfunction "VUSB_18") (pintype "power_in+no_connect"))
    )
  )
)
